# uc4h_node_v2100.net
KiCad netlist of a schematic drawn in EAGLE
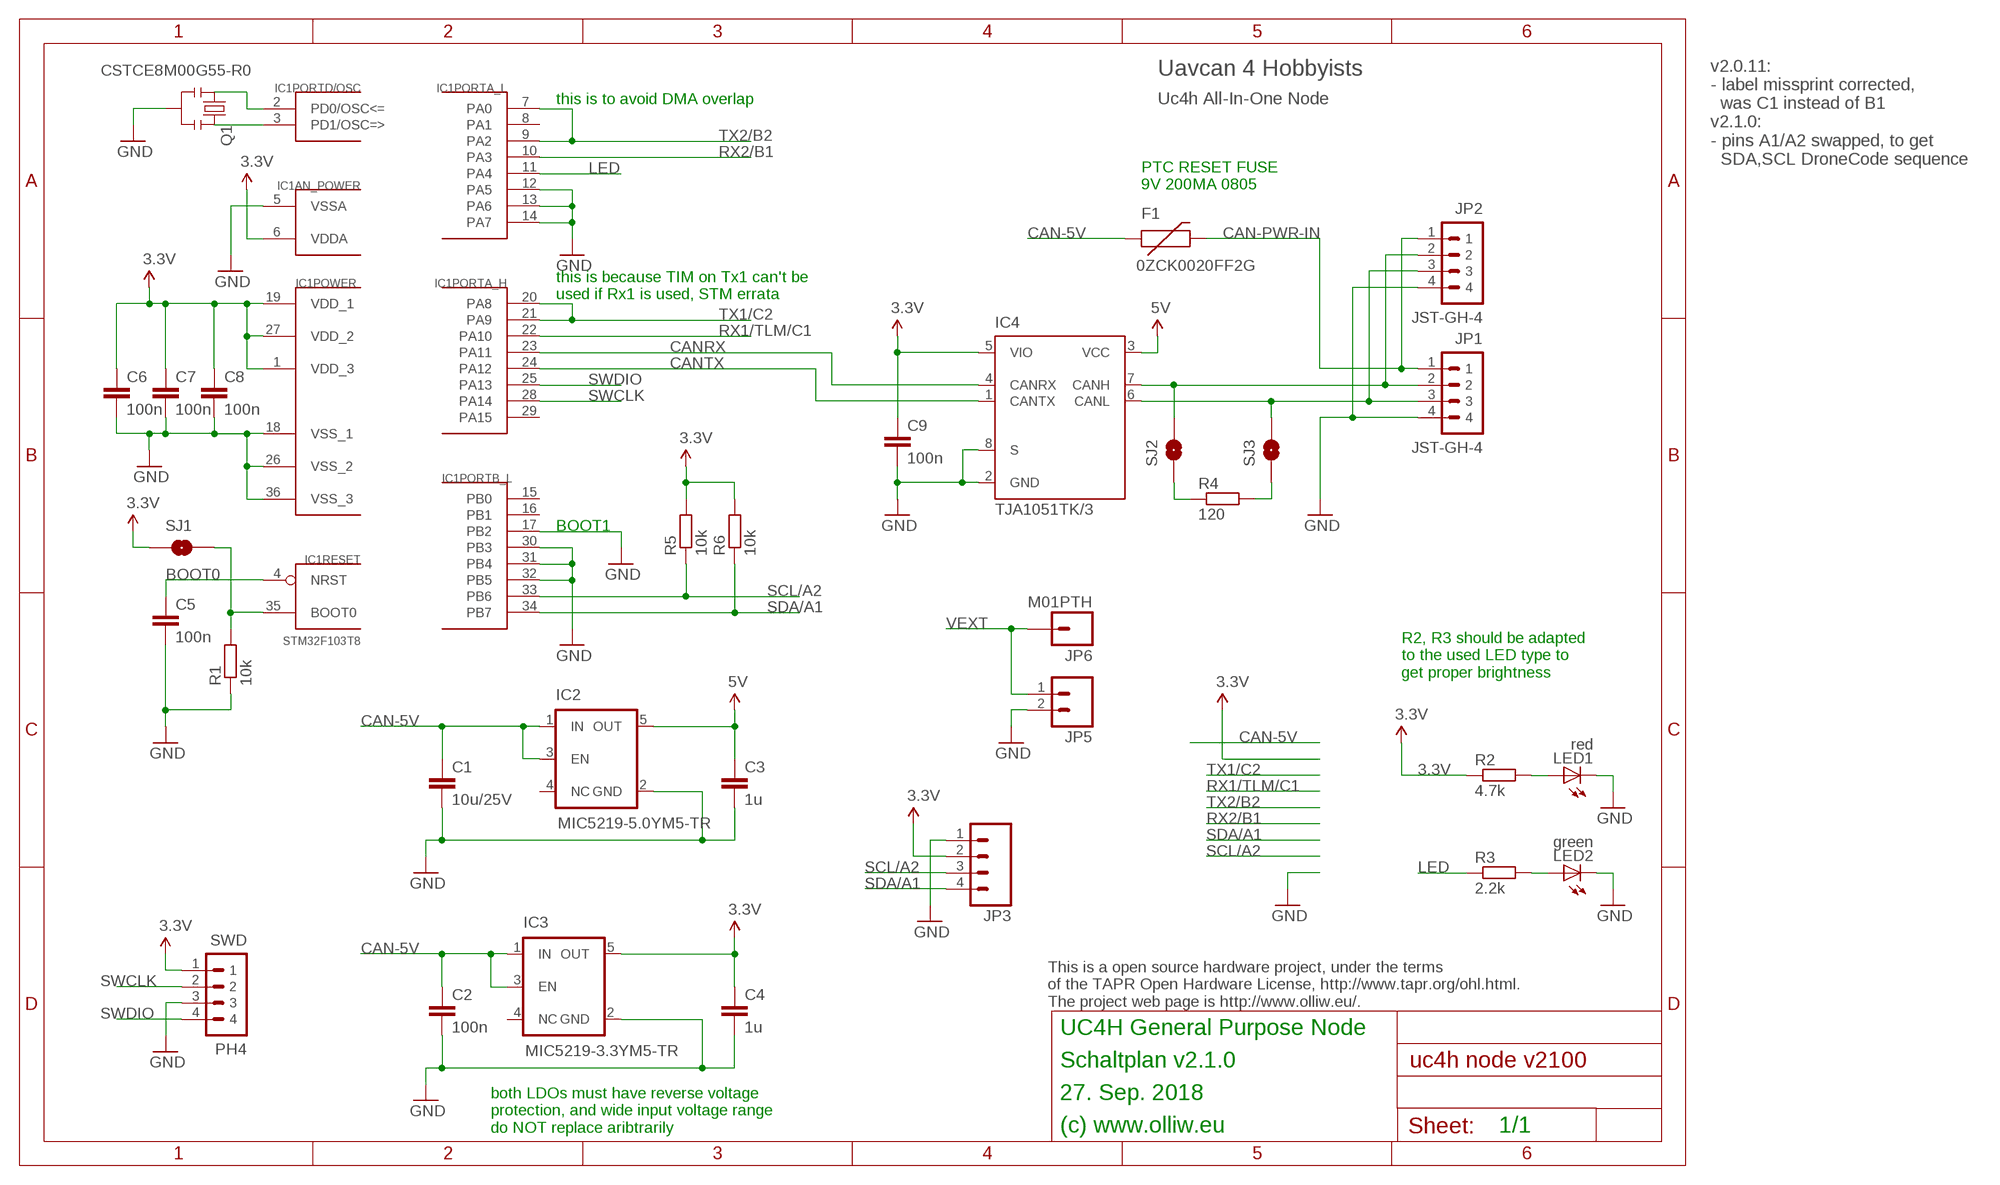
[diagram p0: schematic, sheet 1]

(export (version "E")
  (design (tool "Eeschema 10.0.6"))
  (components
    (comp (ref "C1")
      (value "10u/25V")
      (footprint "eagle-import:C1206")
      (libsource (lib "eagle-import") (part "C-EUC1206"))
    )
    (comp (ref "C2")
      (value "100n")
      (footprint "eagle-import:C0603K")
      (libsource (lib "eagle-import") (part "C-EUC0603K"))
    )
    (comp (ref "C3")
      (value "1u")
      (footprint "eagle-import:C0603K")
      (libsource (lib "eagle-import") (part "C-EUC0603K"))
    )
    (comp (ref "C4")
      (value "1u")
      (footprint "eagle-import:C0603K")
      (libsource (lib "eagle-import") (part "C-EUC0603K"))
    )
    (comp (ref "C5")
      (value "100n")
      (footprint "eagle-import:C0603K")
      (libsource (lib "eagle-import") (part "C-EUC0603K"))
    )
    (comp (ref "C6")
      (value "100n")
      (footprint "eagle-import:C0603K")
      (libsource (lib "eagle-import") (part "C-EUC0603K"))
    )
    (comp (ref "C7")
      (value "100n")
      (footprint "eagle-import:C0603K")
      (libsource (lib "eagle-import") (part "C-EUC0603K"))
    )
    (comp (ref "C8")
      (value "100n")
      (footprint "eagle-import:C0603K")
      (libsource (lib "eagle-import") (part "C-EUC0603K"))
    )
    (comp (ref "C9")
      (value "100n")
      (footprint "eagle-import:C0603K")
      (libsource (lib "eagle-import") (part "C-EUC0603K"))
    )
    (comp (ref "F1")
      (value "0ZCK0020FF2G")
      (footprint "eagle-import:FUSE-0805")
      (libsource (lib "eagle-import") (part "FUSE-PTCFUSE-0805"))
    )
    (comp (ref "IC1")
      (value "STM32F103T8")
      (footprint "eagle-import:VFQFPN36")
      (libsource (lib "eagle-import") (part "STM32F10XTXU6"))
    )
    (comp (ref "IC2")
      (value "MIC5219-5.0YM5-TR")
      (footprint "eagle-import:SOT23-5")
      (libsource (lib "eagle-import") (part "V_REG_TPS76433SOT23-5"))
    )
    (comp (ref "IC3")
      (value "MIC5219-3.3YM5-TR")
      (footprint "eagle-import:SOT23-5")
      (libsource (lib "eagle-import") (part "V_REG_TPS76433SOT23-5"))
    )
    (comp (ref "IC4")
      (value "TJA1051TK/3")
      (footprint "eagle-import:HVSON8")
      (libsource (lib "eagle-import") (part "TJA1051TK/3"))
    )
    (comp (ref "JP1")
      (value "JST-GH-4")
      (footprint "eagle-import:SM04B-GHS-TB")
      (libsource (lib "eagle-import") (part "JST-GH-4"))
    )
    (comp (ref "JP2")
      (value "JST-GH-4")
      (footprint "eagle-import:SM04B-GHS-TB")
      (libsource (lib "eagle-import") (part "JST-GH-4"))
    )
    (comp (ref "JP3")
      (value "M04PTH")
      (footprint "eagle-import:1X04")
      (libsource (lib "eagle-import") (part "M04PTH"))
    )
    (comp (ref "JP5")
      (value "M02PTH")
      (footprint "eagle-import:1X02")
      (libsource (lib "eagle-import") (part "M02PTH"))
    )
    (comp (ref "JP6")
      (value "M01PTH")
      (footprint "eagle-import:1X01")
      (libsource (lib "eagle-import") (part "M01PTH"))
    )
    (comp (ref "LED1")
      (value "red")
      (footprint "eagle-import:CHIPLED_0603")
      (libsource (lib "eagle-import") (part "LEDCHIPLED_0603"))
    )
    (comp (ref "LED2")
      (value "green")
      (footprint "eagle-import:CHIPLED_0603")
      (libsource (lib "eagle-import") (part "LEDCHIPLED_0603"))
    )
    (comp (ref "Q1")
      (value "CSTCE8M00G55-R0")
      (footprint "eagle-import:RESONATOR-SMD")
      (libsource (lib "eagle-import") (part "RESONATORSMD"))
    )
    (comp (ref "R1")
      (value "10k")
      (footprint "eagle-import:R0603")
      (libsource (lib "eagle-import") (part "R-EU_R0603"))
    )
    (comp (ref "R2")
      (value "4.7k")
      (footprint "eagle-import:R0603")
      (libsource (lib "eagle-import") (part "R-EU_R0603"))
    )
    (comp (ref "R3")
      (value "2.2k")
      (footprint "eagle-import:R0603")
      (libsource (lib "eagle-import") (part "R-EU_R0603"))
    )
    (comp (ref "R4")
      (value "120")
      (footprint "eagle-import:R0603")
      (libsource (lib "eagle-import") (part "R-EU_R0603"))
    )
    (comp (ref "R5")
      (value "10k")
      (footprint "eagle-import:R0603")
      (libsource (lib "eagle-import") (part "R-EU_R0603"))
    )
    (comp (ref "R6")
      (value "10k")
      (footprint "eagle-import:R0603")
      (libsource (lib "eagle-import") (part "R-EU_R0603"))
    )
    (comp (ref "SJ1")
      (value "BOOT0")
      (footprint "eagle-import:SJ_2S-NO")
      (libsource (lib "eagle-import") (part "SOLDERJUMPERNO"))
    )
    (comp (ref "SJ2")
      (value "SOLDERJUMPERNO")
      (footprint "eagle-import:SJ_2S-NO")
      (libsource (lib "eagle-import") (part "SOLDERJUMPERNO"))
    )
    (comp (ref "SJ3")
      (value "SOLDERJUMPERNO")
      (footprint "eagle-import:SJ_2S-NO")
      (libsource (lib "eagle-import") (part "SOLDERJUMPERNO"))
    )
    (comp (ref "SWD")
      (value "PH4")
      (footprint "eagle-import:4X1_1P27_OCT_BILEX")
      (libsource (lib "eagle-import") (part "P4X1_1P27-OCT_BILEX"))
    )
  )
  (nets
    (net (code "1") (name "/CAN-5V") (class "Default")
      (node (ref "C1") (pin "1") (pinfunction "1_1") (pintype "passive"))
      (node (ref "C2") (pin "1") (pinfunction "1_1") (pintype "passive"))
      (node (ref "F1") (pin "1") (pinfunction "1_1") (pintype "bidirectional"))
      (node (ref "IC2") (pin "1") (pinfunction "IN_1") (pintype "power_in"))
      (node (ref "IC2") (pin "3") (pinfunction "EN_3") (pintype "input"))
      (node (ref "IC3") (pin "1") (pinfunction "IN_1") (pintype "power_in"))
      (node (ref "IC3") (pin "3") (pinfunction "EN_3") (pintype "input"))
    )
    (net (code "2") (name "/CAN-PWR-IN") (class "Default")
      (node (ref "F1") (pin "2") (pinfunction "2_2") (pintype "bidirectional"))
      (node (ref "JP1") (pin "1") (pinfunction "1_1") (pintype "passive"))
      (node (ref "JP2") (pin "1") (pinfunction "1_1") (pintype "passive"))
    )
    (net (code "3") (name "/CANRX") (class "Default")
      (node (ref "IC1") (pin "23") (pinfunction "PA11_23") (pintype "bidirectional"))
      (node (ref "IC4") (pin "4") (pinfunction "CANRX_4") (pintype "output"))
    )
    (net (code "4") (name "/CANTX") (class "Default")
      (node (ref "IC1") (pin "24") (pinfunction "PA12_24") (pintype "bidirectional"))
      (node (ref "IC4") (pin "1") (pinfunction "CANTX_1") (pintype "input"))
    )
    (net (code "5") (name "/LED") (class "Default")
      (node (ref "IC1") (pin "11") (pinfunction "PA4_11") (pintype "bidirectional"))
      (node (ref "R3") (pin "1") (pinfunction "1_1") (pintype "passive"))
    )
    (net (code "6") (name "/RX1{slash}TLM{slash}C1") (class "Default")
      (node (ref "IC1") (pin "22") (pinfunction "PA10_22") (pintype "bidirectional"))
    )
    (net (code "7") (name "/RX2{slash}B1") (class "Default")
      (node (ref "IC1") (pin "10") (pinfunction "PA3_10") (pintype "bidirectional"))
    )
    (net (code "8") (name "/SCL{slash}A2") (class "Default")
      (node (ref "IC1") (pin "33") (pinfunction "PB6_33") (pintype "bidirectional"))
      (node (ref "JP3") (pin "3") (pinfunction "3_3") (pintype "passive"))
      (node (ref "R5") (pin "1") (pinfunction "1_1") (pintype "passive"))
    )
    (net (code "9") (name "/SDA{slash}A1") (class "Default")
      (node (ref "IC1") (pin "34") (pinfunction "PB7_34") (pintype "bidirectional"))
      (node (ref "JP3") (pin "4") (pinfunction "4_4") (pintype "passive"))
      (node (ref "R6") (pin "1") (pinfunction "1_1") (pintype "passive"))
    )
    (net (code "10") (name "/SWCLK") (class "Default")
      (node (ref "IC1") (pin "28") (pinfunction "PA14_28") (pintype "bidirectional"))
      (node (ref "SWD") (pin "2") (pinfunction "2_2") (pintype "passive"))
    )
    (net (code "11") (name "/SWDIO") (class "Default")
      (node (ref "IC1") (pin "25") (pinfunction "PA13_25") (pintype "bidirectional"))
      (node (ref "SWD") (pin "4") (pinfunction "4_4") (pintype "passive"))
    )
    (net (code "12") (name "/TX1{slash}C2") (class "Default")
      (node (ref "IC1") (pin "20") (pinfunction "PA8_20") (pintype "bidirectional"))
      (node (ref "IC1") (pin "21") (pinfunction "PA9_21") (pintype "bidirectional"))
    )
    (net (code "13") (name "/TX2{slash}B2") (class "Default")
      (node (ref "IC1") (pin "7") (pinfunction "PA0_7") (pintype "bidirectional"))
      (node (ref "IC1") (pin "9") (pinfunction "PA2_9") (pintype "bidirectional"))
    )
    (net (code "14") (name "/VEXT") (class "Default")
      (node (ref "JP5") (pin "1") (pinfunction "1_1") (pintype "passive"))
      (node (ref "JP6") (pin "1") (pinfunction "1_1") (pintype "passive"))
    )
    (net (code "15") (name "3.3V") (class "Default")
      (node (ref "C4") (pin "1") (pinfunction "1_1") (pintype "passive"))
      (node (ref "C6") (pin "1") (pinfunction "1_1") (pintype "passive"))
      (node (ref "C7") (pin "1") (pinfunction "1_1") (pintype "passive"))
      (node (ref "C8") (pin "1") (pinfunction "1_1") (pintype "passive"))
      (node (ref "C9") (pin "1") (pinfunction "1_1") (pintype "passive"))
      (node (ref "IC1") (pin "1") (pinfunction "VDD_3_1") (pintype "power_in"))
      (node (ref "IC1") (pin "19") (pinfunction "VDD_1_19") (pintype "power_in"))
      (node (ref "IC1") (pin "27") (pinfunction "VDD_2_27") (pintype "power_in"))
      (node (ref "IC1") (pin "6") (pinfunction "VDDA_6") (pintype "power_in"))
      (node (ref "IC3") (pin "5") (pinfunction "OUT_5") (pintype "output"))
      (node (ref "IC4") (pin "5") (pinfunction "VIO_5") (pintype "power_in"))
      (node (ref "JP3") (pin "2") (pinfunction "2_2") (pintype "passive"))
      (node (ref "R2") (pin "1") (pinfunction "1_1") (pintype "passive"))
      (node (ref "R5") (pin "2") (pinfunction "2_2") (pintype "passive"))
      (node (ref "R6") (pin "2") (pinfunction "2_2") (pintype "passive"))
      (node (ref "SJ1") (pin "1") (pinfunction "1_1") (pintype "passive"))
      (node (ref "SWD") (pin "1") (pinfunction "1_1") (pintype "passive"))
    )
    (net (code "16") (name "5V") (class "Default")
      (node (ref "C3") (pin "1") (pinfunction "1_1") (pintype "passive"))
      (node (ref "IC2") (pin "5") (pinfunction "OUT_5") (pintype "output"))
      (node (ref "IC4") (pin "3") (pinfunction "VCC_3") (pintype "power_in"))
    )
    (net (code "17") (name "GND") (class "Default")
      (node (ref "C1") (pin "2") (pinfunction "2_2") (pintype "passive"))
      (node (ref "C2") (pin "2") (pinfunction "2_2") (pintype "passive"))
      (node (ref "C3") (pin "2") (pinfunction "2_2") (pintype "passive"))
      (node (ref "C4") (pin "2") (pinfunction "2_2") (pintype "passive"))
      (node (ref "C5") (pin "2") (pinfunction "2_2") (pintype "passive"))
      (node (ref "C6") (pin "2") (pinfunction "2_2") (pintype "passive"))
      (node (ref "C7") (pin "2") (pinfunction "2_2") (pintype "passive"))
      (node (ref "C8") (pin "2") (pinfunction "2_2") (pintype "passive"))
      (node (ref "C9") (pin "2") (pinfunction "2_2") (pintype "passive"))
      (node (ref "IC1") (pin "12") (pinfunction "PA5_12") (pintype "bidirectional"))
      (node (ref "IC1") (pin "13") (pinfunction "PA6_13") (pintype "bidirectional"))
      (node (ref "IC1") (pin "14") (pinfunction "PA7_14") (pintype "bidirectional"))
      (node (ref "IC1") (pin "17") (pinfunction "PB2_17") (pintype "bidirectional"))
      (node (ref "IC1") (pin "18") (pinfunction "VSS_1_18") (pintype "power_in"))
      (node (ref "IC1") (pin "26") (pinfunction "VSS_2_26") (pintype "power_in"))
      (node (ref "IC1") (pin "30") (pinfunction "PB3_30") (pintype "bidirectional"))
      (node (ref "IC1") (pin "31") (pinfunction "PB4_31") (pintype "bidirectional"))
      (node (ref "IC1") (pin "32") (pinfunction "PB5_32") (pintype "bidirectional"))
      (node (ref "IC1") (pin "36") (pinfunction "VSS_3_36") (pintype "power_in"))
      (node (ref "IC1") (pin "5") (pinfunction "VSSA_5") (pintype "power_in"))
      (node (ref "IC2") (pin "2") (pinfunction "GND_2") (pintype "power_in"))
      (node (ref "IC3") (pin "2") (pinfunction "GND_2") (pintype "power_in"))
      (node (ref "IC4") (pin "2") (pinfunction "GND_2") (pintype "power_in"))
      (node (ref "IC4") (pin "8") (pinfunction "S_8") (pintype "input"))
      (node (ref "JP1") (pin "4") (pinfunction "4_4") (pintype "passive"))
      (node (ref "JP2") (pin "4") (pinfunction "4_4") (pintype "passive"))
      (node (ref "JP3") (pin "1") (pinfunction "1_1") (pintype "passive"))
      (node (ref "JP5") (pin "2") (pinfunction "2_2") (pintype "passive"))
      (node (ref "LED1") (pin "C") (pinfunction "C_C") (pintype "passive"))
      (node (ref "LED2") (pin "C") (pinfunction "C_C") (pintype "passive"))
      (node (ref "Q1") (pin "2") (pinfunction "2_2") (pintype "passive"))
      (node (ref "R1") (pin "1") (pinfunction "1_1") (pintype "passive"))
      (node (ref "SWD") (pin "3") (pinfunction "3_3") (pintype "passive"))
    )
    (net (code "18") (name "Net-(IC1E-PD0{slash}OSC<=)") (class "Default")
      (node (ref "IC1") (pin "2") (pinfunction "PD0/OSC<=_2") (pintype "bidirectional"))
      (node (ref "Q1") (pin "1") (pinfunction "1_1") (pintype "passive"))
    )
    (net (code "19") (name "Net-(IC1E-PD1{slash}OSC=>)") (class "Default")
      (node (ref "IC1") (pin "3") (pinfunction "PD1/OSC=>_3") (pintype "bidirectional"))
      (node (ref "Q1") (pin "3") (pinfunction "3_3") (pintype "passive"))
    )
    (net (code "20") (name "Net-(IC1G-BOOT0)") (class "Default")
      (node (ref "IC1") (pin "35") (pinfunction "BOOT0_35") (pintype "input"))
      (node (ref "R1") (pin "2") (pinfunction "2_2") (pintype "passive"))
      (node (ref "SJ1") (pin "2") (pinfunction "2_2") (pintype "passive"))
    )
    (net (code "21") (name "Net-(IC1G-NRST)") (class "Default")
      (node (ref "C5") (pin "1") (pinfunction "1_1") (pintype "passive"))
      (node (ref "IC1") (pin "4") (pinfunction "NRST_4") (pintype "input"))
    )
    (net (code "22") (name "Net-(IC4-CANH)") (class "Default")
      (node (ref "IC4") (pin "7") (pinfunction "CANH_7") (pintype "bidirectional"))
      (node (ref "JP1") (pin "2") (pinfunction "2_2") (pintype "passive"))
      (node (ref "JP2") (pin "2") (pinfunction "2_2") (pintype "passive"))
      (node (ref "SJ2") (pin "2") (pinfunction "2_2") (pintype "passive"))
    )
    (net (code "23") (name "Net-(IC4-CANL)") (class "Default")
      (node (ref "IC4") (pin "6") (pinfunction "CANL_6") (pintype "bidirectional"))
      (node (ref "JP1") (pin "3") (pinfunction "3_3") (pintype "passive"))
      (node (ref "JP2") (pin "3") (pinfunction "3_3") (pintype "passive"))
      (node (ref "SJ3") (pin "2") (pinfunction "2_2") (pintype "passive"))
    )
    (net (code "24") (name "Net-(LED1-PadA)") (class "Default")
      (node (ref "LED1") (pin "A") (pinfunction "A_A") (pintype "passive"))
      (node (ref "R2") (pin "2") (pinfunction "2_2") (pintype "passive"))
    )
    (net (code "25") (name "Net-(LED2-PadA)") (class "Default")
      (node (ref "LED2") (pin "A") (pinfunction "A_A") (pintype "passive"))
      (node (ref "R3") (pin "2") (pinfunction "2_2") (pintype "passive"))
    )
    (net (code "26") (name "Net-(R4-Pad1)") (class "Default")
      (node (ref "R4") (pin "1") (pinfunction "1_1") (pintype "passive"))
      (node (ref "SJ2") (pin "1") (pinfunction "1_1") (pintype "passive"))
    )
    (net (code "27") (name "Net-(R4-Pad2)") (class "Default")
      (node (ref "R4") (pin "2") (pinfunction "2_2") (pintype "passive"))
      (node (ref "SJ3") (pin "1") (pinfunction "1_1") (pintype "passive"))
    )
    (net (code "28") (name "unconnected-(IC1B-PA15-Pad29)") (class "Default")
      (node (ref "IC1") (pin "29") (pinfunction "PA15_29") (pintype "bidirectional"))
    )
    (net (code "29") (name "unconnected-(IC1C-PA1-Pad8)") (class "Default")
      (node (ref "IC1") (pin "8") (pinfunction "PA1_8") (pintype "bidirectional"))
    )
    (net (code "30") (name "unconnected-(IC1D-PB0-Pad15)") (class "Default")
      (node (ref "IC1") (pin "15") (pinfunction "PB0_15") (pintype "bidirectional"))
    )
    (net (code "31") (name "unconnected-(IC1D-PB1-Pad16)") (class "Default")
      (node (ref "IC1") (pin "16") (pinfunction "PB1_16") (pintype "bidirectional"))
    )
    (net (code "32") (name "unconnected-(IC2-NC-Pad4)") (class "Default")
      (node (ref "IC2") (pin "4") (pinfunction "NC_4") (pintype "passive"))
    )
    (net (code "33") (name "unconnected-(IC3-NC-Pad4)") (class "Default")
      (node (ref "IC3") (pin "4") (pinfunction "NC_4") (pintype "passive"))
    )
  )
)
